# Calliope_mini_rev0_3_3_gipfel.net
KiCad netlist of a schematic drawn in EAGLE
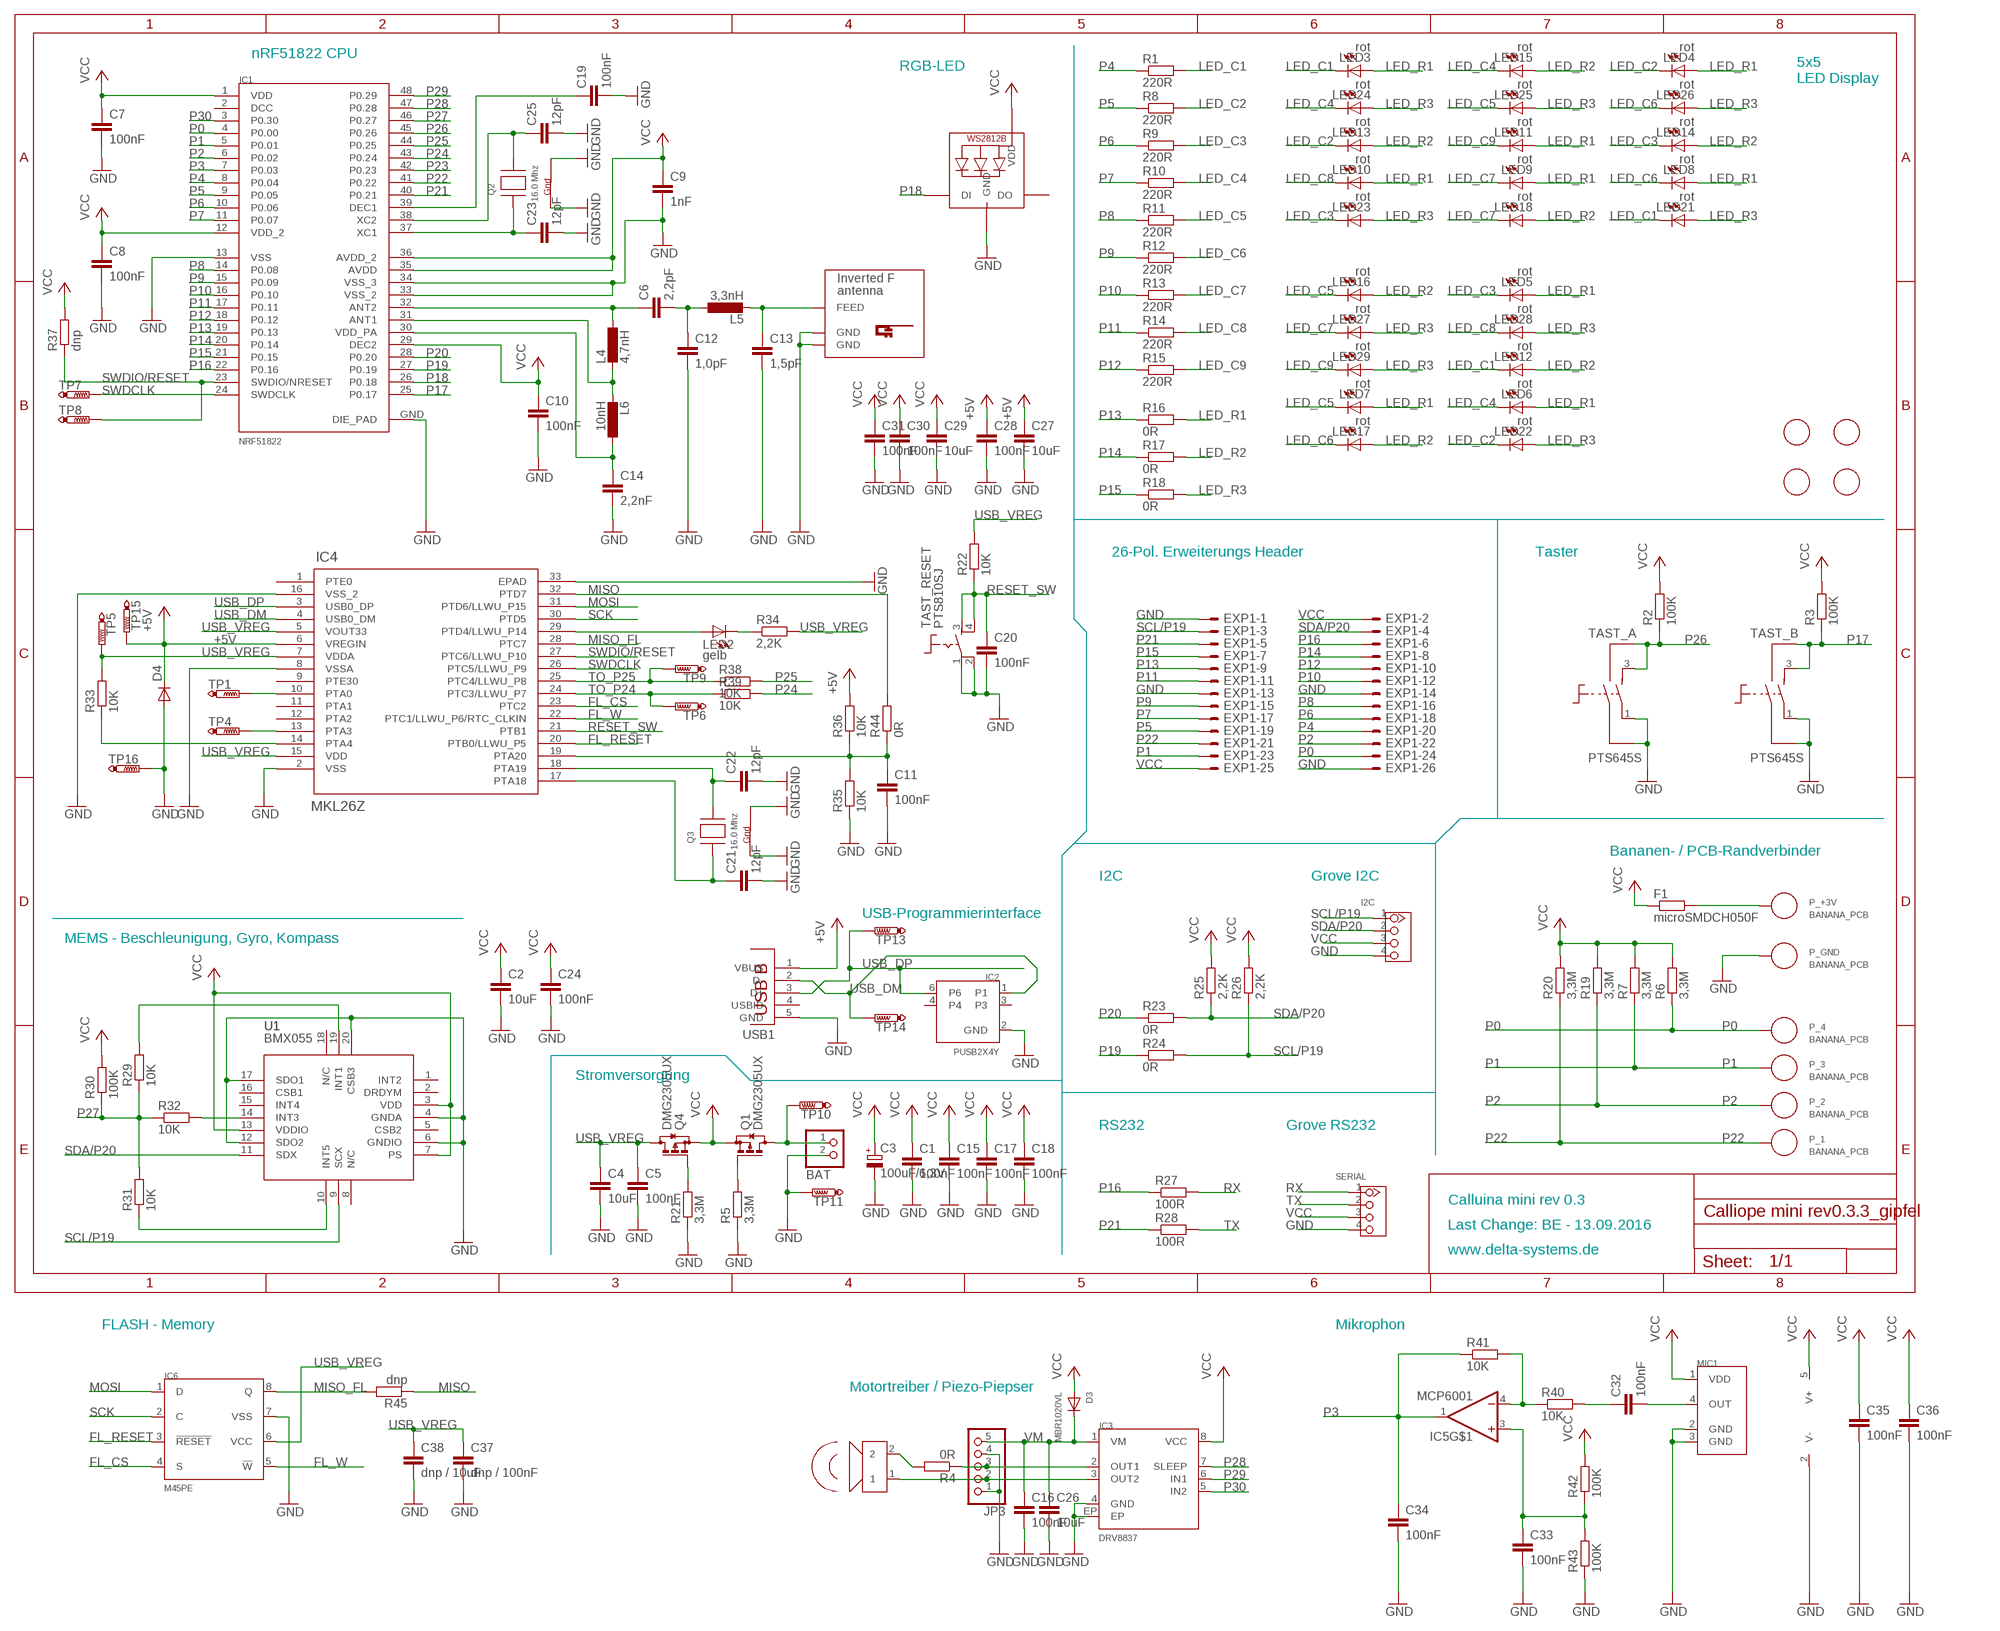
[diagram p0: schematic, sheet 1]

(export (version "E")
  (design (tool "Eeschema 10.0.6"))
  (components
    (comp (ref "BAT")
      (value "JST_2PIN-SMT-RA")
      (footprint "eagle-import:JST-PH-2-SMT-RA")
      (libsource (lib "eagle-import") (part "JST_2PIN-SMT-RA"))
    )
    (comp (ref "C1")
      (value "100nF")
      (footprint "eagle-import:0402")
      (libsource (lib "eagle-import") (part "C-EU0402"))
    )
    (comp (ref "C2")
      (value "10uF")
      (footprint "eagle-import:0603")
      (libsource (lib "eagle-import") (part "C-EU0603"))
    )
    (comp (ref "C3")
      (value "100uF/6,3V")
      (footprint "eagle-import:D_7343-31R")
      (libsource (lib "eagle-import") (part "CPOL-EUD/7343-31R"))
    )
    (comp (ref "C4")
      (value "10uF")
      (footprint "eagle-import:0603")
      (libsource (lib "eagle-import") (part "C-EU0603"))
    )
    (comp (ref "C5")
      (value "100nF")
      (footprint "eagle-import:0402")
      (libsource (lib "eagle-import") (part "C-EU0402"))
    )
    (comp (ref "C6")
      (value "2,2pF")
      (footprint "eagle-import:0402")
      (libsource (lib "eagle-import") (part "C-EU0402"))
    )
    (comp (ref "C7")
      (value "100nF")
      (footprint "eagle-import:0402")
      (libsource (lib "eagle-import") (part "C-EU0402"))
    )
    (comp (ref "C8")
      (value "100nF")
      (footprint "eagle-import:0402")
      (libsource (lib "eagle-import") (part "C-EU0402"))
    )
    (comp (ref "C9")
      (value "1nF")
      (footprint "eagle-import:0402")
      (libsource (lib "eagle-import") (part "C-EU0402"))
    )
    (comp (ref "C10")
      (value "100nF")
      (footprint "eagle-import:0402")
      (libsource (lib "eagle-import") (part "C-EU0402"))
    )
    (comp (ref "C11")
      (value "100nF")
      (footprint "eagle-import:0402")
      (libsource (lib "eagle-import") (part "C-EU0402"))
    )
    (comp (ref "C12")
      (value "1,0pF")
      (footprint "eagle-import:0402")
      (libsource (lib "eagle-import") (part "C-EU0402"))
    )
    (comp (ref "C13")
      (value "1,5pF")
      (footprint "eagle-import:0402")
      (libsource (lib "eagle-import") (part "C-EU0402"))
    )
    (comp (ref "C14")
      (value "2,2nF")
      (footprint "eagle-import:0402")
      (libsource (lib "eagle-import") (part "C-EU0402"))
    )
    (comp (ref "C15")
      (value "100nF")
      (footprint "eagle-import:0402")
      (libsource (lib "eagle-import") (part "C-EU0402"))
    )
    (comp (ref "C16")
      (value "100nF")
      (footprint "eagle-import:0402")
      (libsource (lib "eagle-import") (part "C-EU0402"))
    )
    (comp (ref "C17")
      (value "100nF")
      (footprint "eagle-import:0402")
      (libsource (lib "eagle-import") (part "C-EU0402"))
    )
    (comp (ref "C18")
      (value "100nF")
      (footprint "eagle-import:0402")
      (libsource (lib "eagle-import") (part "C-EU0402"))
    )
    (comp (ref "C19")
      (value "100nF")
      (footprint "eagle-import:0402")
      (libsource (lib "eagle-import") (part "C-EU0402"))
    )
    (comp (ref "C20")
      (value "100nF")
      (footprint "eagle-import:0402")
      (libsource (lib "eagle-import") (part "C-EU0402"))
    )
    (comp (ref "C21")
      (value "12pF")
      (footprint "eagle-import:0402")
      (libsource (lib "eagle-import") (part "C-EU0402"))
    )
    (comp (ref "C22")
      (value "12pF")
      (footprint "eagle-import:0402")
      (libsource (lib "eagle-import") (part "C-EU0402"))
    )
    (comp (ref "C23")
      (value "12pF")
      (footprint "eagle-import:0402")
      (libsource (lib "eagle-import") (part "C-EU0402"))
    )
    (comp (ref "C24")
      (value "100nF")
      (footprint "eagle-import:0402")
      (libsource (lib "eagle-import") (part "C-EU0402"))
    )
    (comp (ref "C25")
      (value "12pF")
      (footprint "eagle-import:0402")
      (libsource (lib "eagle-import") (part "C-EU0402"))
    )
    (comp (ref "C26")
      (value "10uF")
      (footprint "eagle-import:0603")
      (libsource (lib "eagle-import") (part "C-EU0603"))
    )
    (comp (ref "C27")
      (value "10uF")
      (footprint "eagle-import:0603")
      (libsource (lib "eagle-import") (part "C-EU0603"))
    )
    (comp (ref "C28")
      (value "100nF")
      (footprint "eagle-import:0402")
      (libsource (lib "eagle-import") (part "C-EU0402"))
    )
    (comp (ref "C29")
      (value "10uF")
      (footprint "eagle-import:0603")
      (libsource (lib "eagle-import") (part "C-EU0603"))
    )
    (comp (ref "C30")
      (value "100nF")
      (footprint "eagle-import:0402")
      (libsource (lib "eagle-import") (part "C-EU0402"))
    )
    (comp (ref "C31")
      (value "100nF")
      (footprint "eagle-import:0402")
      (libsource (lib "eagle-import") (part "C-EU0402"))
    )
    (comp (ref "C32")
      (value "100nF")
      (footprint "eagle-import:0402")
      (libsource (lib "eagle-import") (part "C-EU0402"))
    )
    (comp (ref "C33")
      (value "100nF")
      (footprint "eagle-import:0402")
      (libsource (lib "eagle-import") (part "C-EU0402"))
    )
    (comp (ref "C34")
      (value "100nF")
      (footprint "eagle-import:0402")
      (libsource (lib "eagle-import") (part "C-EU0402"))
    )
    (comp (ref "C35")
      (value "100nF")
      (footprint "eagle-import:0402")
      (libsource (lib "eagle-import") (part "C-EU0402"))
    )
    (comp (ref "C36")
      (value "100nF")
      (footprint "eagle-import:0402")
      (libsource (lib "eagle-import") (part "C-EU0402"))
    )
    (comp (ref "C37")
      (value "dnp / 100nF")
      (footprint "eagle-import:0402")
      (libsource (lib "eagle-import") (part "C-EU0402"))
    )
    (comp (ref "C38")
      (value "dnp / 10uF")
      (footprint "eagle-import:0603")
      (libsource (lib "eagle-import") (part "C-EU0603"))
    )
    (comp (ref "D3")
      (value "MBR1020VL")
      (footprint "eagle-import:SOD-123FL")
      (libsource (lib "eagle-import") (part "DIODE_SOD-123FL"))
    )
    (comp (ref "D4")
      (value "DIODE-SOD323-R")
      (footprint "eagle-import:SOD323-R")
      (libsource (lib "eagle-import") (part "DIODE-SOD323-R"))
    )
    (comp (ref "EXP1")
      (value "ML26E")
      (footprint "eagle-import:ML26")
      (libsource (lib "eagle-import") (part "ML26?E"))
    )
    (comp (ref "F1")
      (value "microSMDCH050F")
      (footprint "eagle-import:R1210")
      (libsource (lib "eagle-import") (part "R-EU_R1210"))
    )
    (comp (ref "I2C")
      (value "GROVE-CONNECTOR-DIP(4P-2.0)")
      (footprint "eagle-import:HW4-2.0")
      (libsource (lib "eagle-import") (part "GROVE-CONNECTOR-DIP(4P-2.0)"))
    )
    (comp (ref "IC1")
      (value "NRF51822")
      (footprint "eagle-import:QFN48")
      (libsource (lib "eagle-import") (part "NRF51822"))
    )
    (comp (ref "IC2")
      (value "PUSB2X4Y")
      (footprint "eagle-import:SOT363")
      (libsource (lib "eagle-import") (part "PUSB2X4Y"))
    )
    (comp (ref "IC3")
      (value "DRV8837")
      (footprint "eagle-import:WSON8")
      (libsource (lib "eagle-import") (part "DRV8837"))
    )
    (comp (ref "IC4")
      (value "MKL26Z")
      (footprint "eagle-import:QFN_32_5X5X0P9")
      (libsource (lib "eagle-import") (part "MKL26Z"))
    )
    (comp (ref "IC5")
      (value "MCP6001")
      (footprint "eagle-import:SOT23-5")
      (libsource (lib "eagle-import") (part "OPAMP_SINGLESOT23-5"))
    )
    (comp (ref "IC6")
      (value "M45PE")
      (footprint "eagle-import:VQFN8_6X5")
      (libsource (lib "eagle-import") (part "M45PE"))
    )
    (comp (ref "JP3")
      (value "PINHD-1X5")
      (footprint "eagle-import:1X05")
      (libsource (lib "eagle-import") (part "PINHD-1X5"))
    )
    (comp (ref "L4")
      (value "4,7nH")
      (footprint "eagle-import:0402")
      (libsource (lib "eagle-import") (part "L-EU0402"))
    )
    (comp (ref "L5")
      (value "3,3nH")
      (footprint "eagle-import:0402")
      (libsource (lib "eagle-import") (part "L-EU0402"))
    )
    (comp (ref "L6")
      (value "10nH")
      (footprint "eagle-import:0402")
      (libsource (lib "eagle-import") (part "L-EU0402"))
    )
    (comp (ref "LED1")
      (value "SK6812MINI")
      (footprint "eagle-import:LED3535")
      (libsource (lib "eagle-import") (part "WS2812B3535"))
    )
    (comp (ref "LED2")
      (value "gelb")
      (footprint "eagle-import:CHIPLED_0603")
      (libsource (lib "eagle-import") (part "LEDCHIPLED_0603"))
    )
    (comp (ref "LED3")
      (value "rot")
      (footprint "eagle-import:CHIPLED_0603")
      (libsource (lib "eagle-import") (part "LEDCHIPLED_0603"))
    )
    (comp (ref "LED4")
      (value "rot")
      (footprint "eagle-import:CHIPLED_0603")
      (libsource (lib "eagle-import") (part "LEDCHIPLED_0603"))
    )
    (comp (ref "LED5")
      (value "rot")
      (footprint "eagle-import:CHIPLED_0603")
      (libsource (lib "eagle-import") (part "LEDCHIPLED_0603"))
    )
    (comp (ref "LED6")
      (value "rot")
      (footprint "eagle-import:CHIPLED_0603")
      (libsource (lib "eagle-import") (part "LEDCHIPLED_0603"))
    )
    (comp (ref "LED7")
      (value "rot")
      (footprint "eagle-import:CHIPLED_0603")
      (libsource (lib "eagle-import") (part "LEDCHIPLED_0603"))
    )
    (comp (ref "LED8")
      (value "rot")
      (footprint "eagle-import:CHIPLED_0603")
      (libsource (lib "eagle-import") (part "LEDCHIPLED_0603"))
    )
    (comp (ref "LED9")
      (value "rot")
      (footprint "eagle-import:CHIPLED_0603")
      (libsource (lib "eagle-import") (part "LEDCHIPLED_0603"))
    )
    (comp (ref "LED10")
      (value "rot")
      (footprint "eagle-import:CHIPLED_0603")
      (libsource (lib "eagle-import") (part "LEDCHIPLED_0603"))
    )
    (comp (ref "LED11")
      (value "rot")
      (footprint "eagle-import:CHIPLED_0603")
      (libsource (lib "eagle-import") (part "LEDCHIPLED_0603"))
    )
    (comp (ref "LED12")
      (value "rot")
      (footprint "eagle-import:CHIPLED_0603")
      (libsource (lib "eagle-import") (part "LEDCHIPLED_0603"))
    )
    (comp (ref "LED13")
      (value "rot")
      (footprint "eagle-import:CHIPLED_0603")
      (libsource (lib "eagle-import") (part "LEDCHIPLED_0603"))
    )
    (comp (ref "LED14")
      (value "rot")
      (footprint "eagle-import:CHIPLED_0603")
      (libsource (lib "eagle-import") (part "LEDCHIPLED_0603"))
    )
    (comp (ref "LED15")
      (value "rot")
      (footprint "eagle-import:CHIPLED_0603")
      (libsource (lib "eagle-import") (part "LEDCHIPLED_0603"))
    )
    (comp (ref "LED16")
      (value "rot")
      (footprint "eagle-import:CHIPLED_0603")
      (libsource (lib "eagle-import") (part "LEDCHIPLED_0603"))
    )
    (comp (ref "LED17")
      (value "rot")
      (footprint "eagle-import:CHIPLED_0603")
      (libsource (lib "eagle-import") (part "LEDCHIPLED_0603"))
    )
    (comp (ref "LED18")
      (value "rot")
      (footprint "eagle-import:CHIPLED_0603")
      (libsource (lib "eagle-import") (part "LEDCHIPLED_0603"))
    )
    (comp (ref "LED21")
      (value "rot")
      (footprint "eagle-import:CHIPLED_0603")
      (libsource (lib "eagle-import") (part "LEDCHIPLED_0603"))
    )
    (comp (ref "LED22")
      (value "rot")
      (footprint "eagle-import:CHIPLED_0603")
      (libsource (lib "eagle-import") (part "LEDCHIPLED_0603"))
    )
    (comp (ref "LED23")
      (value "rot")
      (footprint "eagle-import:CHIPLED_0603")
      (libsource (lib "eagle-import") (part "LEDCHIPLED_0603"))
    )
    (comp (ref "LED24")
      (value "rot")
      (footprint "eagle-import:CHIPLED_0603")
      (libsource (lib "eagle-import") (part "LEDCHIPLED_0603"))
    )
    (comp (ref "LED25")
      (value "rot")
      (footprint "eagle-import:CHIPLED_0603")
      (libsource (lib "eagle-import") (part "LEDCHIPLED_0603"))
    )
    (comp (ref "LED26")
      (value "rot")
      (footprint "eagle-import:CHIPLED_0603")
      (libsource (lib "eagle-import") (part "LEDCHIPLED_0603"))
    )
    (comp (ref "LED27")
      (value "rot")
      (footprint "eagle-import:CHIPLED_0603")
      (libsource (lib "eagle-import") (part "LEDCHIPLED_0603"))
    )
    (comp (ref "LED28")
      (value "rot")
      (footprint "eagle-import:CHIPLED_0603")
      (libsource (lib "eagle-import") (part "LEDCHIPLED_0603"))
    )
    (comp (ref "LED29")
      (value "rot")
      (footprint "eagle-import:CHIPLED_0603")
      (libsource (lib "eagle-import") (part "LEDCHIPLED_0603"))
    )
    (comp (ref "MIC1")
      (value "SPU0410HR5H-PB")
      (footprint "eagle-import:SPU0410HR5H-PB")
      (libsource (lib "eagle-import") (part "SPU0410HR5H-PB"))
    )
    (comp (ref "P_+3V")
      (value "BANANA_PCB")
      (footprint "eagle-import:BANANA_REC")
      (libsource (lib "eagle-import") (part "BANANA_PCB"))
    )
    (comp (ref "P_1")
      (value "BANANA_PCB")
      (footprint "eagle-import:BANANA_REC")
      (libsource (lib "eagle-import") (part "BANANA_PCB"))
    )
    (comp (ref "P_2")
      (value "BANANA_PCB")
      (footprint "eagle-import:BANANA_REC")
      (libsource (lib "eagle-import") (part "BANANA_PCB"))
    )
    (comp (ref "P_3")
      (value "BANANA_PCB")
      (footprint "eagle-import:BANANA_REC")
      (libsource (lib "eagle-import") (part "BANANA_PCB"))
    )
    (comp (ref "P_4")
      (value "BANANA_PCB")
      (footprint "eagle-import:BANANA_REC")
      (libsource (lib "eagle-import") (part "BANANA_PCB"))
    )
    (comp (ref "P_GND")
      (value "BANANA_PCB")
      (footprint "eagle-import:BANANA_REC")
      (libsource (lib "eagle-import") (part "BANANA_PCB"))
    )
    (comp (ref "Q1")
      (value "DMG2305UX")
      (footprint "eagle-import:SOT23")
      (libsource (lib "eagle-import") (part "BSS84"))
    )
    (comp (ref "Q2")
      (value "16.0 Mhz")
      (footprint "eagle-import:NX3225")
      (libsource (lib "eagle-import") (part "XTAL-4-3225"))
    )
    (comp (ref "Q3")
      (value "16.0 Mhz")
      (footprint "eagle-import:NX3225")
      (libsource (lib "eagle-import") (part "XTAL-4-3225"))
    )
    (comp (ref "Q4")
      (value "DMG2305UX")
      (footprint "eagle-import:SOT23")
      (libsource (lib "eagle-import") (part "BSS84"))
    )
    (comp (ref "R1")
      (value "220R")
      (footprint "eagle-import:0402")
      (libsource (lib "eagle-import") (part "R-EU_0402"))
    )
    (comp (ref "R2")
      (value "100K")
      (footprint "eagle-import:0402")
      (libsource (lib "eagle-import") (part "R-EU_0402"))
    )
    (comp (ref "R3")
      (value "100K")
      (footprint "eagle-import:0402")
      (libsource (lib "eagle-import") (part "R-EU_0402"))
    )
    (comp (ref "R4")
      (value "0R")
      (footprint "eagle-import:0402")
      (libsource (lib "eagle-import") (part "R-EU_0402"))
    )
    (comp (ref "R5")
      (value "3,3M")
      (footprint "eagle-import:0402")
      (libsource (lib "eagle-import") (part "R-EU_0402"))
    )
    (comp (ref "R6")
      (value "3,3M")
      (footprint "eagle-import:0402")
      (libsource (lib "eagle-import") (part "R-EU_0402"))
    )
    (comp (ref "R7")
      (value "3,3M")
      (footprint "eagle-import:0402")
      (libsource (lib "eagle-import") (part "R-EU_0402"))
    )
    (comp (ref "R8")
      (value "220R")
      (footprint "eagle-import:0402")
      (libsource (lib "eagle-import") (part "R-EU_0402"))
    )
    (comp (ref "R9")
      (value "220R")
      (footprint "eagle-import:0402")
      (libsource (lib "eagle-import") (part "R-EU_0402"))
    )
    (comp (ref "R10")
      (value "220R")
      (footprint "eagle-import:0402")
      (libsource (lib "eagle-import") (part "R-EU_0402"))
    )
    (comp (ref "R11")
      (value "220R")
      (footprint "eagle-import:0402")
      (libsource (lib "eagle-import") (part "R-EU_0402"))
    )
    (comp (ref "R12")
      (value "220R")
      (footprint "eagle-import:0402")
      (libsource (lib "eagle-import") (part "R-EU_0402"))
    )
    (comp (ref "R13")
      (value "220R")
      (footprint "eagle-import:0402")
      (libsource (lib "eagle-import") (part "R-EU_0402"))
    )
    (comp (ref "R14")
      (value "220R")
      (footprint "eagle-import:0402")
      (libsource (lib "eagle-import") (part "R-EU_0402"))
    )
    (comp (ref "R15")
      (value "220R")
      (footprint "eagle-import:0402")
      (libsource (lib "eagle-import") (part "R-EU_0402"))
    )
    (comp (ref "R16")
      (value "0R")
      (footprint "eagle-import:0402")
      (libsource (lib "eagle-import") (part "R-EU_0402"))
    )
    (comp (ref "R17")
      (value "0R")
      (footprint "eagle-import:0402")
      (libsource (lib "eagle-import") (part "R-EU_0402"))
    )
    (comp (ref "R18")
      (value "0R")
      (footprint "eagle-import:0402")
      (libsource (lib "eagle-import") (part "R-EU_0402"))
    )
    (comp (ref "R19")
      (value "3,3M")
      (footprint "eagle-import:0402")
      (libsource (lib "eagle-import") (part "R-EU_0402"))
    )
    (comp (ref "R20")
      (value "3,3M")
      (footprint "eagle-import:0402")
      (libsource (lib "eagle-import") (part "R-EU_0402"))
    )
    (comp (ref "R21")
      (value "3,3M")
      (footprint "eagle-import:0402")
      (libsource (lib "eagle-import") (part "R-EU_0402"))
    )
    (comp (ref "R22")
      (value "10K")
      (footprint "eagle-import:0402")
      (libsource (lib "eagle-import") (part "R-EU_0402"))
    )
    (comp (ref "R23")
      (value "0R")
      (footprint "eagle-import:0402")
      (libsource (lib "eagle-import") (part "R-EU_0402"))
    )
    (comp (ref "R24")
      (value "0R")
      (footprint "eagle-import:0402")
      (libsource (lib "eagle-import") (part "R-EU_0402"))
    )
    (comp (ref "R25")
      (value "2,2K")
      (footprint "eagle-import:0402")
      (libsource (lib "eagle-import") (part "R-EU_0402"))
    )
    (comp (ref "R26")
      (value "2,2K")
      (footprint "eagle-import:0402")
      (libsource (lib "eagle-import") (part "R-EU_0402"))
    )
    (comp (ref "R27")
      (value "100R")
      (footprint "eagle-import:0402")
      (libsource (lib "eagle-import") (part "R-EU_0402"))
    )
    (comp (ref "R28")
      (value "100R")
      (footprint "eagle-import:0402")
      (libsource (lib "eagle-import") (part "R-EU_0402"))
    )
    (comp (ref "R29")
      (value "10K")
      (footprint "eagle-import:0402")
      (libsource (lib "eagle-import") (part "R-EU_0402"))
    )
    (comp (ref "R30")
      (value "100K")
      (footprint "eagle-import:0402")
      (libsource (lib "eagle-import") (part "R-EU_0402"))
    )
    (comp (ref "R31")
      (value "10K")
      (footprint "eagle-import:0402")
      (libsource (lib "eagle-import") (part "R-EU_0402"))
    )
    (comp (ref "R32")
      (value "10K")
      (footprint "eagle-import:0402")
      (libsource (lib "eagle-import") (part "R-EU_0402"))
    )
    (comp (ref "R33")
      (value "10K")
      (footprint "eagle-import:0402")
      (libsource (lib "eagle-import") (part "R-EU_0402"))
    )
    (comp (ref "R34")
      (value "2,2K")
      (footprint "eagle-import:0402")
      (libsource (lib "eagle-import") (part "R-EU_0402"))
    )
    (comp (ref "R35")
      (value "10K")
      (footprint "eagle-import:0402")
      (libsource (lib "eagle-import") (part "R-EU_0402"))
    )
    (comp (ref "R36")
      (value "10K")
      (footprint "eagle-import:0402")
      (libsource (lib "eagle-import") (part "R-EU_0402"))
    )
    (comp (ref "R37")
      (value "dnp")
      (footprint "eagle-import:0402")
      (libsource (lib "eagle-import") (part "R-EU_0402"))
    )
    (comp (ref "R38")
      (value "10K")
      (footprint "eagle-import:0402")
      (libsource (lib "eagle-import") (part "R-EU_0402"))
    )
    (comp (ref "R39")
      (value "10K")
      (footprint "eagle-import:0402")
      (libsource (lib "eagle-import") (part "R-EU_0402"))
    )
    (comp (ref "R40")
      (value "10K")
      (footprint "eagle-import:0402")
      (libsource (lib "eagle-import") (part "R-EU_0402"))
    )
    (comp (ref "R41")
      (value "10K")
      (footprint "eagle-import:0402")
      (libsource (lib "eagle-import") (part "R-EU_0402"))
    )
    (comp (ref "R42")
      (value "100K")
      (footprint "eagle-import:0402")
      (libsource (lib "eagle-import") (part "R-EU_0402"))
    )
    (comp (ref "R43")
      (value "100K")
      (footprint "eagle-import:0402")
      (libsource (lib "eagle-import") (part "R-EU_0402"))
    )
    (comp (ref "R44")
      (value "0R")
      (footprint "eagle-import:0402")
      (libsource (lib "eagle-import") (part "R-EU_0402"))
    )
    (comp (ref "R45")
      (value "dnp")
      (footprint "eagle-import:0402")
      (libsource (lib "eagle-import") (part "R-EU_0402"))
    )
    (comp (ref "SERIAL")
      (value "GROVE-CONNECTOR-DIP(4P-2.0)")
      (footprint "eagle-import:HW4-2.0")
      (libsource (lib "eagle-import") (part "GROVE-CONNECTOR-DIP(4P-2.0)"))
    )
    (comp (ref "SPK1")
      (value "PKMCS0909E4000-R1")
      (footprint "eagle-import:PKMCS")
      (libsource (lib "eagle-import") (part "PKMCS0909E4000-R1"))
    )
    (comp (ref "TAST_A")
      (value "PTS645S")
      (footprint "eagle-import:PTS645S")
      (libsource (lib "eagle-import") (part "PTS645S"))
    )
    (comp (ref "TAST_B")
      (value "PTS645S")
      (footprint "eagle-import:PTS645S")
      (libsource (lib "eagle-import") (part "PTS645S"))
    )
    (comp (ref "TAST_RESET")
      (value "PTS810SJ")
      (footprint "eagle-import:PTS810")
      (libsource (lib "eagle-import") (part "PTS810SJ"))
    )
    (comp (ref "TP1")
      (value "PTR1B1,27")
      (footprint "eagle-import:B1,27")
      (libsource (lib "eagle-import") (part "PTR1B1,27"))
    )
    (comp (ref "TP4")
      (value "PTR1B1,27")
      (footprint "eagle-import:B1,27")
      (libsource (lib "eagle-import") (part "PTR1B1,27"))
    )
    (comp (ref "TP5")
      (value "PTR1B1,27")
      (footprint "eagle-import:B1,27")
      (libsource (lib "eagle-import") (part "PTR1B1,27"))
    )
    (comp (ref "TP6")
      (value "PTR1B1,27")
      (footprint "eagle-import:B1,27")
      (libsource (lib "eagle-import") (part "PTR1B1,27"))
    )
    (comp (ref "TP7")
      (value "PTR1B1,27")
      (footprint "eagle-import:B1,27")
      (libsource (lib "eagle-import") (part "PTR1B1,27"))
    )
    (comp (ref "TP8")
      (value "PTR1B1,27")
      (footprint "eagle-import:B1,27")
      (libsource (lib "eagle-import") (part "PTR1B1,27"))
    )
    (comp (ref "TP9")
      (value "PTR1B1,27")
      (footprint "eagle-import:B1,27")
      (libsource (lib "eagle-import") (part "PTR1B1,27"))
    )
    (comp (ref "TP10")
      (value "PTR1B1,27")
      (footprint "eagle-import:B1,27")
      (libsource (lib "eagle-import") (part "PTR1B1,27"))
    )
    (comp (ref "TP11")
      (value "PTR1B1,27")
      (footprint "eagle-import:B1,27")
      (libsource (lib "eagle-import") (part "PTR1B1,27"))
    )
    (comp (ref "TP13")
      (value "PTR1B1,27")
      (footprint "eagle-import:B1,27")
      (libsource (lib "eagle-import") (part "PTR1B1,27"))
    )
    (comp (ref "TP14")
      (value "PTR1B1,27")
      (footprint "eagle-import:B1,27")
      (libsource (lib "eagle-import") (part "PTR1B1,27"))
    )
    (comp (ref "TP15")
      (value "PTR1B1,27")
      (footprint "eagle-import:B1,27")
      (libsource (lib "eagle-import") (part "PTR1B1,27"))
    )
    (comp (ref "TP16")
      (value "PTR1B1,27")
      (footprint "eagle-import:B1,27")
      (libsource (lib "eagle-import") (part "PTR1B1,27"))
    )
    (comp (ref "U$2")
      (value "INVERTED_F_ANTENNA")
      (footprint "eagle-import:DN0007+0_MIRROR")
      (libsource (lib "eagle-import") (part "INVERTED_F_ANTENNA"))
    )
    (comp (ref "U$5")
      (value "FIDUCIAL")
      (footprint "eagle-import:FIDUCIAL_1MM")
      (libsource (lib "eagle-import") (part "FIDUCIAL"))
    )
    (comp (ref "U$6")
      (value "FIDUCIAL")
      (footprint "eagle-import:FIDUCIAL_1MM")
      (libsource (lib "eagle-import") (part "FIDUCIAL"))
    )
    (comp (ref "U$7")
      (value "FIDUCIAL")
      (footprint "eagle-import:FIDUCIAL_1MM")
      (libsource (lib "eagle-import") (part "FIDUCIAL"))
    )
    (comp (ref "U$8")
      (value "FIDUCIAL")
      (footprint "eagle-import:FIDUCIAL_1MM")
      (libsource (lib "eagle-import") (part "FIDUCIAL"))
    )
    (comp (ref "U1")
      (value "BMX055")
      (footprint "eagle-import:BMX055")
      (libsource (lib "eagle-import") (part "BMX055"))
    )
    (comp (ref "USB1")
      (value "USB_47642-0011")
      (footprint "eagle-import:47642-0011")
      (libsource (lib "eagle-import") (part "USB_47642-0011"))
    )
  )
  (nets
    (net (code "1") (name "+5V") (class "Default")
      (node (ref "C27") (pin "1") (pinfunction "1_1") (pintype "passive"))
      (node (ref "C28") (pin "1") (pinfunction "1_1") (pintype "passive"))
      (node (ref "D4") (pin "C") (pinfunction "C_C") (pintype "passive"))
      (node (ref "IC4") (pin "6") (pinfunction "VREGIN_6") (pintype "input"))
      (node (ref "R36") (pin "2") (pinfunction "2_2") (pintype "passive"))
      (node (ref "TP15") (pin "TP") (pinfunction "TP_TP") (pintype "input"))
      (node (ref "USB1") (pin "1") (pinfunction "VBUS_1") (pintype "bidirectional"))
    )
    (net (code "2") (name "/FL_CS") (class "Default")
      (node (ref "IC4") (pin "23") (pinfunction "PTC2_23") (pintype "bidirectional"))
      (node (ref "IC6") (pin "4") (pinfunction "S_4") (pintype "bidirectional"))
    )
    (net (code "3") (name "/FL_RESET") (class "Default")
      (node (ref "IC4") (pin "20") (pinfunction "PTB0/LLWU_P5_20") (pintype "bidirectional"))
      (node (ref "IC6") (pin "3") (pinfunction "~{RESET}_3") (pintype "bidirectional"))
    )
    (net (code "4") (name "/FL_W") (class "Default")
      (node (ref "IC4") (pin "22") (pinfunction "PTC1/LLWU_P6/RTC_CLKIN_22") (pintype "bidirectional"))
      (node (ref "IC6") (pin "5") (pinfunction "~{W}_5") (pintype "bidirectional"))
    )
    (net (code "5") (name "/LED_C1") (class "Default")
      (node (ref "LED12") (pin "A") (pinfunction "A_A") (pintype "passive"))
      (node (ref "LED21") (pin "A") (pinfunction "A_A") (pintype "passive"))
      (node (ref "LED3") (pin "A") (pinfunction "A_A") (pintype "passive"))
      (node (ref "R1") (pin "2") (pinfunction "2_2") (pintype "passive"))
    )
    (net (code "6") (name "/LED_C2") (class "Default")
      (node (ref "LED13") (pin "A") (pinfunction "A_A") (pintype "passive"))
      (node (ref "LED22") (pin "A") (pinfunction "A_A") (pintype "passive"))
      (node (ref "LED4") (pin "A") (pinfunction "A_A") (pintype "passive"))
      (node (ref "R8") (pin "2") (pinfunction "2_2") (pintype "passive"))
    )
    (net (code "7") (name "/LED_C3") (class "Default")
      (node (ref "LED14") (pin "A") (pinfunction "A_A") (pintype "passive"))
      (node (ref "LED23") (pin "A") (pinfunction "A_A") (pintype "passive"))
      (node (ref "LED5") (pin "A") (pinfunction "A_A") (pintype "passive"))
      (node (ref "R9") (pin "2") (pinfunction "2_2") (pintype "passive"))
    )
    (net (code "8") (name "/LED_C4") (class "Default")
      (node (ref "LED15") (pin "A") (pinfunction "A_A") (pintype "passive"))
      (node (ref "LED24") (pin "A") (pinfunction "A_A") (pintype "passive"))
      (node (ref "LED6") (pin "A") (pinfunction "A_A") (pintype "passive"))
      (node (ref "R10") (pin "2") (pinfunction "2_2") (pintype "passive"))
    )
    (net (code "9") (name "/LED_C5") (class "Default")
      (node (ref "LED16") (pin "A") (pinfunction "A_A") (pintype "passive"))
      (node (ref "LED25") (pin "A") (pinfunction "A_A") (pintype "passive"))
      (node (ref "LED7") (pin "A") (pinfunction "A_A") (pintype "passive"))
      (node (ref "R11") (pin "2") (pinfunction "2_2") (pintype "passive"))
    )
    (net (code "10") (name "/LED_C6") (class "Default")
      (node (ref "LED17") (pin "A") (pinfunction "A_A") (pintype "passive"))
      (node (ref "LED26") (pin "A") (pinfunction "A_A") (pintype "passive"))
      (node (ref "LED8") (pin "A") (pinfunction "A_A") (pintype "passive"))
      (node (ref "R12") (pin "2") (pinfunction "2_2") (pintype "passive"))
    )
    (net (code "11") (name "/LED_C7") (class "Default")
      (node (ref "LED18") (pin "A") (pinfunction "A_A") (pintype "passive"))
      (node (ref "LED27") (pin "A") (pinfunction "A_A") (pintype "passive"))
      (node (ref "LED9") (pin "A") (pinfunction "A_A") (pintype "passive"))
      (node (ref "R13") (pin "2") (pinfunction "2_2") (pintype "passive"))
    )
    (net (code "12") (name "/LED_C8") (class "Default")
      (node (ref "LED10") (pin "A") (pinfunction "A_A") (pintype "passive"))
      (node (ref "LED28") (pin "A") (pinfunction "A_A") (pintype "passive"))
      (node (ref "R14") (pin "2") (pinfunction "2_2") (pintype "passive"))
    )
    (net (code "13") (name "/LED_C9") (class "Default")
      (node (ref "LED11") (pin "A") (pinfunction "A_A") (pintype "passive"))
      (node (ref "LED29") (pin "A") (pinfunction "A_A") (pintype "passive"))
      (node (ref "R15") (pin "2") (pinfunction "2_2") (pintype "passive"))
    )
    (net (code "14") (name "/LED_R1") (class "Default")
      (node (ref "LED10") (pin "C") (pinfunction "C_C") (pintype "passive"))
      (node (ref "LED11") (pin "C") (pinfunction "C_C") (pintype "passive"))
      (node (ref "LED3") (pin "C") (pinfunction "C_C") (pintype "passive"))
      (node (ref "LED4") (pin "C") (pinfunction "C_C") (pintype "passive"))
      (node (ref "LED5") (pin "C") (pinfunction "C_C") (pintype "passive"))
      (node (ref "LED6") (pin "C") (pinfunction "C_C") (pintype "passive"))
      (node (ref "LED7") (pin "C") (pinfunction "C_C") (pintype "passive"))
      (node (ref "LED8") (pin "C") (pinfunction "C_C") (pintype "passive"))
      (node (ref "LED9") (pin "C") (pinfunction "C_C") (pintype "passive"))
      (node (ref "R16") (pin "2") (pinfunction "2_2") (pintype "passive"))
    )
    (net (code "15") (name "/LED_R2") (class "Default")
      (node (ref "LED12") (pin "C") (pinfunction "C_C") (pintype "passive"))
      (node (ref "LED13") (pin "C") (pinfunction "C_C") (pintype "passive"))
      (node (ref "LED14") (pin "C") (pinfunction "C_C") (pintype "passive"))
      (node (ref "LED15") (pin "C") (pinfunction "C_C") (pintype "passive"))
      (node (ref "LED16") (pin "C") (pinfunction "C_C") (pintype "passive"))
      (node (ref "LED17") (pin "C") (pinfunction "C_C") (pintype "passive"))
      (node (ref "LED18") (pin "C") (pinfunction "C_C") (pintype "passive"))
      (node (ref "R17") (pin "2") (pinfunction "2_2") (pintype "passive"))
    )
    (net (code "16") (name "/LED_R3") (class "Default")
      (node (ref "LED21") (pin "C") (pinfunction "C_C") (pintype "passive"))
      (node (ref "LED22") (pin "C") (pinfunction "C_C") (pintype "passive"))
      (node (ref "LED23") (pin "C") (pinfunction "C_C") (pintype "passive"))
      (node (ref "LED24") (pin "C") (pinfunction "C_C") (pintype "passive"))
      (node (ref "LED25") (pin "C") (pinfunction "C_C") (pintype "passive"))
      (node (ref "LED26") (pin "C") (pinfunction "C_C") (pintype "passive"))
      (node (ref "LED27") (pin "C") (pinfunction "C_C") (pintype "passive"))
      (node (ref "LED28") (pin "C") (pinfunction "C_C") (pintype "passive"))
      (node (ref "LED29") (pin "C") (pinfunction "C_C") (pintype "passive"))
      (node (ref "R18") (pin "2") (pinfunction "2_2") (pintype "passive"))
    )
    (net (code "17") (name "/MISO") (class "Default")
      (node (ref "IC4") (pin "32") (pinfunction "PTD7_32") (pintype "bidirectional"))
      (node (ref "R44") (pin "2") (pinfunction "2_2") (pintype "passive"))
      (node (ref "R45") (pin "1") (pinfunction "1_1") (pintype "passive"))
    )
    (net (code "18") (name "/MISO_FL") (class "Default")
      (node (ref "IC4") (pin "28") (pinfunction "PTC7_28") (pintype "bidirectional"))
      (node (ref "IC6") (pin "8") (pinfunction "Q_8") (pintype "bidirectional"))
      (node (ref "R45") (pin "2") (pinfunction "2_2") (pintype "passive"))
    )
    (net (code "19") (name "/MOSI") (class "Default")
      (node (ref "IC4") (pin "31") (pinfunction "PTD6/LLWU_P15_31") (pintype "bidirectional"))
      (node (ref "IC6") (pin "1") (pinfunction "D_1") (pintype "bidirectional"))
    )
    (net (code "20") (name "/P0") (class "Default")
      (node (ref "EXP1") (pin "24") (pinfunction "S_24") (pintype "passive"))
      (node (ref "IC1") (pin "4") (pinfunction "P0.00_4") (pintype "bidirectional"))
      (node (ref "P_4") (pin "1") (pinfunction "1_1") (pintype "bidirectional"))
      (node (ref "R6") (pin "1") (pinfunction "1_1") (pintype "passive"))
    )
    (net (code "21") (name "/P1") (class "Default")
      (node (ref "EXP1") (pin "23") (pinfunction "S_23") (pintype "passive"))
      (node (ref "IC1") (pin "5") (pinfunction "P0.01_5") (pintype "bidirectional"))
      (node (ref "P_3") (pin "1") (pinfunction "1_1") (pintype "bidirectional"))
      (node (ref "R7") (pin "1") (pinfunction "1_1") (pintype "passive"))
    )
    (net (code "22") (name "/P2") (class "Default")
      (node (ref "EXP1") (pin "22") (pinfunction "S_22") (pintype "passive"))
      (node (ref "IC1") (pin "6") (pinfunction "P0.02_6") (pintype "bidirectional"))
      (node (ref "P_2") (pin "1") (pinfunction "1_1") (pintype "bidirectional"))
      (node (ref "R19") (pin "1") (pinfunction "1_1") (pintype "passive"))
    )
    (net (code "23") (name "/P3") (class "Default")
      (node (ref "C34") (pin "1") (pinfunction "1_1") (pintype "passive"))
      (node (ref "IC1") (pin "7") (pinfunction "P0.03_7") (pintype "bidirectional"))
      (node (ref "IC5") (pin "1") (pinfunction "OUT_1") (pintype "output"))
      (node (ref "R41") (pin "1") (pinfunction "1_1") (pintype "passive"))
    )
    (net (code "24") (name "/P4") (class "Default")
      (node (ref "EXP1") (pin "20") (pinfunction "S_20") (pintype "passive"))
      (node (ref "IC1") (pin "8") (pinfunction "P0.04_8") (pintype "bidirectional"))
      (node (ref "R1") (pin "1") (pinfunction "1_1") (pintype "passive"))
    )
    (net (code "25") (name "/P5") (class "Default")
      (node (ref "EXP1") (pin "19") (pinfunction "S_19") (pintype "passive"))
      (node (ref "IC1") (pin "9") (pinfunction "P0.05_9") (pintype "bidirectional"))
      (node (ref "R8") (pin "1") (pinfunction "1_1") (pintype "passive"))
    )
    (net (code "26") (name "/P6") (class "Default")
      (node (ref "EXP1") (pin "18") (pinfunction "S_18") (pintype "passive"))
      (node (ref "IC1") (pin "10") (pinfunction "P0.06_10") (pintype "bidirectional"))
      (node (ref "R9") (pin "1") (pinfunction "1_1") (pintype "passive"))
    )
    (net (code "27") (name "/P7") (class "Default")
      (node (ref "EXP1") (pin "17") (pinfunction "S_17") (pintype "passive"))
      (node (ref "IC1") (pin "11") (pinfunction "P0.07_11") (pintype "bidirectional"))
      (node (ref "R10") (pin "1") (pinfunction "1_1") (pintype "passive"))
    )
    (net (code "28") (name "/P8") (class "Default")
      (node (ref "EXP1") (pin "16") (pinfunction "S_16") (pintype "passive"))
      (node (ref "IC1") (pin "14") (pinfunction "P0.08_14") (pintype "bidirectional"))
      (node (ref "R11") (pin "1") (pinfunction "1_1") (pintype "passive"))
    )
    (net (code "29") (name "/P9") (class "Default")
      (node (ref "EXP1") (pin "15") (pinfunction "S_15") (pintype "passive"))
      (node (ref "IC1") (pin "15") (pinfunction "P0.09_15") (pintype "bidirectional"))
      (node (ref "R12") (pin "1") (pinfunction "1_1") (pintype "passive"))
    )
    (net (code "30") (name "/P10") (class "Default")
      (node (ref "EXP1") (pin "12") (pinfunction "S_12") (pintype "passive"))
      (node (ref "IC1") (pin "16") (pinfunction "P0.10_16") (pintype "bidirectional"))
      (node (ref "R13") (pin "1") (pinfunction "1_1") (pintype "passive"))
    )
    (net (code "31") (name "/P11") (class "Default")
      (node (ref "EXP1") (pin "11") (pinfunction "S_11") (pintype "passive"))
      (node (ref "IC1") (pin "17") (pinfunction "P0.11_17") (pintype "bidirectional"))
      (node (ref "R14") (pin "1") (pinfunction "1_1") (pintype "passive"))
    )
    (net (code "32") (name "/P12") (class "Default")
      (node (ref "EXP1") (pin "10") (pinfunction "S_10") (pintype "passive"))
      (node (ref "IC1") (pin "18") (pinfunction "P0.12_18") (pintype "bidirectional"))
      (node (ref "R15") (pin "1") (pinfunction "1_1") (pintype "passive"))
    )
    (net (code "33") (name "/P13") (class "Default")
      (node (ref "EXP1") (pin "9") (pinfunction "S_9") (pintype "passive"))
      (node (ref "IC1") (pin "19") (pinfunction "P0.13_19") (pintype "bidirectional"))
      (node (ref "R16") (pin "1") (pinfunction "1_1") (pintype "passive"))
    )
    (net (code "34") (name "/P14") (class "Default")
      (node (ref "EXP1") (pin "8") (pinfunction "S_8") (pintype "passive"))
      (node (ref "IC1") (pin "20") (pinfunction "P0.14_20") (pintype "bidirectional"))
      (node (ref "R17") (pin "1") (pinfunction "1_1") (pintype "passive"))
    )
    (net (code "35") (name "/P15") (class "Default")
      (node (ref "EXP1") (pin "7") (pinfunction "S_7") (pintype "passive"))
      (node (ref "IC1") (pin "21") (pinfunction "P0.15_21") (pintype "bidirectional"))
      (node (ref "R18") (pin "1") (pinfunction "1_1") (pintype "passive"))
    )
    (net (code "36") (name "/P16") (class "Default")
      (node (ref "EXP1") (pin "6") (pinfunction "S_6") (pintype "passive"))
      (node (ref "IC1") (pin "22") (pinfunction "P0.16_22") (pintype "bidirectional"))
      (node (ref "R27") (pin "1") (pinfunction "1_1") (pintype "passive"))
    )
    (net (code "37") (name "/P17") (class "Default")
      (node (ref "IC1") (pin "25") (pinfunction "P0.17_25") (pintype "bidirectional"))
      (node (ref "R3") (pin "1") (pinfunction "1_1") (pintype "passive"))
      (node (ref "TAST_B") (pin "3") (pinfunction "S1_3") (pintype "passive"))
      (node (ref "TAST_B") (pin "4") (pinfunction "S2_4") (pintype "passive"))
    )
    (net (code "38") (name "/P18") (class "Default")
      (node (ref "IC1") (pin "26") (pinfunction "P0.18_26") (pintype "bidirectional"))
      (node (ref "LED1") (pin "1") (pinfunction "DI_1") (pintype "input"))
    )
    (net (code "39") (name "/P19") (class "Default")
      (node (ref "IC1") (pin "27") (pinfunction "P0.19_27") (pintype "bidirectional"))
      (node (ref "R24") (pin "1") (pinfunction "1_1") (pintype "passive"))
    )
    (net (code "40") (name "/P20") (class "Default")
      (node (ref "IC1") (pin "28") (pinfunction "P0.20_28") (pintype "bidirectional"))
      (node (ref "R23") (pin "1") (pinfunction "1_1") (pintype "passive"))
    )
    (net (code "41") (name "/P21") (class "Default")
      (node (ref "EXP1") (pin "5") (pinfunction "S_5") (pintype "passive"))
      (node (ref "IC1") (pin "40") (pinfunction "P0.21_40") (pintype "bidirectional"))
      (node (ref "R28") (pin "1") (pinfunction "1_1") (pintype "passive"))
    )
    (net (code "42") (name "/P22") (class "Default")
      (node (ref "EXP1") (pin "21") (pinfunction "S_21") (pintype "passive"))
      (node (ref "IC1") (pin "41") (pinfunction "P0.22_41") (pintype "bidirectional"))
      (node (ref "P_1") (pin "1") (pinfunction "1_1") (pintype "bidirectional"))
      (node (ref "R20") (pin "1") (pinfunction "1_1") (pintype "passive"))
    )
    (net (code "43") (name "/P23") (class "Default")
      (node (ref "IC1") (pin "42") (pinfunction "P0.23_42") (pintype "bidirectional"))
    )
    (net (code "44") (name "/P24") (class "Default")
      (node (ref "IC1") (pin "43") (pinfunction "P0.24_43") (pintype "bidirectional"))
      (node (ref "R39") (pin "2") (pinfunction "2_2") (pintype "passive"))
    )
    (net (code "45") (name "/P25") (class "Default")
      (node (ref "IC1") (pin "44") (pinfunction "P0.25_44") (pintype "bidirectional"))
      (node (ref "R38") (pin "2") (pinfunction "2_2") (pintype "passive"))
    )
    (net (code "46") (name "/P26") (class "Default")
      (node (ref "IC1") (pin "45") (pinfunction "P0.26_45") (pintype "bidirectional"))
      (node (ref "R2") (pin "1") (pinfunction "1_1") (pintype "passive"))
      (node (ref "TAST_A") (pin "3") (pinfunction "S1_3") (pintype "passive"))
      (node (ref "TAST_A") (pin "4") (pinfunction "S2_4") (pintype "passive"))
    )
    (net (code "47") (name "/P27") (class "Default")
      (node (ref "IC1") (pin "46") (pinfunction "P0.27_46") (pintype "bidirectional"))
      (node (ref "R29") (pin "1") (pinfunction "1_1") (pintype "passive"))
      (node (ref "R30") (pin "1") (pinfunction "1_1") (pintype "passive"))
      (node (ref "R31") (pin "2") (pinfunction "2_2") (pintype "passive"))
      (node (ref "R32") (pin "1") (pinfunction "1_1") (pintype "passive"))
    )
    (net (code "48") (name "/P28") (class "Default")
      (node (ref "IC1") (pin "47") (pinfunction "P0.28_47") (pintype "bidirectional"))
      (node (ref "IC3") (pin "7") (pinfunction "SLEEP_7") (pintype "bidirectional"))
    )
    (net (code "49") (name "/P29") (class "Default")
      (node (ref "IC1") (pin "48") (pinfunction "P0.29_48") (pintype "bidirectional"))
      (node (ref "IC3") (pin "6") (pinfunction "IN1_6") (pintype "bidirectional"))
    )
    (net (code "50") (name "/P30") (class "Default")
      (node (ref "IC1") (pin "3") (pinfunction "P0.30_3") (pintype "bidirectional"))
      (node (ref "IC3") (pin "5") (pinfunction "IN2_5") (pintype "bidirectional"))
    )
    (net (code "51") (name "/RESET_SW") (class "Default")
      (node (ref "C20") (pin "1") (pinfunction "1_1") (pintype "passive"))
      (node (ref "IC4") (pin "21") (pinfunction "PTB1_21") (pintype "bidirectional"))
      (node (ref "R22") (pin "1") (pinfunction "1_1") (pintype "passive"))
      (node (ref "TAST_RESET") (pin "3") (pinfunction "S_3") (pintype "passive"))
      (node (ref "TAST_RESET") (pin "4") (pinfunction "S1_4") (pintype "passive"))
    )
    (net (code "52") (name "/RX") (class "Default")
      (node (ref "R27") (pin "2") (pinfunction "2_2") (pintype "passive"))
      (node (ref "SERIAL") (pin "1") (pinfunction "1_1") (pintype "bidirectional"))
    )
    (net (code "53") (name "/SCK") (class "Default")
      (node (ref "IC4") (pin "30") (pinfunction "PTD5_30") (pintype "bidirectional"))
      (node (ref "IC6") (pin "2") (pinfunction "C_2") (pintype "bidirectional"))
    )
    (net (code "54") (name "/SCL{slash}P19") (class "Default")
      (node (ref "EXP1") (pin "3") (pinfunction "S_3") (pintype "passive"))
      (node (ref "I2C") (pin "1") (pinfunction "1_1") (pintype "bidirectional"))
      (node (ref "R24") (pin "2") (pinfunction "2_2") (pintype "passive"))
      (node (ref "R26") (pin "1") (pinfunction "1_1") (pintype "passive"))
      (node (ref "U1") (pin "9") (pinfunction "SCX_9") (pintype "bidirectional"))
    )
    (net (code "55") (name "/SDA{slash}P20") (class "Default")
      (node (ref "EXP1") (pin "4") (pinfunction "S_4") (pintype "passive"))
      (node (ref "I2C") (pin "2") (pinfunction "2_2") (pintype "bidirectional"))
      (node (ref "R23") (pin "2") (pinfunction "2_2") (pintype "passive"))
      (node (ref "R25") (pin "1") (pinfunction "1_1") (pintype "passive"))
      (node (ref "U1") (pin "11") (pinfunction "SDX_11") (pintype "bidirectional"))
    )
    (net (code "56") (name "/SWDCLK") (class "Default")
      (node (ref "IC1") (pin "24") (pinfunction "SWDCLK_24") (pintype "bidirectional"))
      (node (ref "IC4") (pin "26") (pinfunction "PTC5/LLWU_P9_26") (pintype "bidirectional"))
      (node (ref "TP7") (pin "TP") (pinfunction "TP_TP") (pintype "input"))
    )
    (net (code "57") (name "/SWDIO{slash}RESET") (class "Default")
      (node (ref "IC1") (pin "23") (pinfunction "SWDIO/NRESET_23") (pintype "bidirectional"))
      (node (ref "IC4") (pin "27") (pinfunction "PTC6/LLWU_P10_27") (pintype "bidirectional"))
      (node (ref "R37") (pin "1") (pinfunction "1_1") (pintype "passive"))
      (node (ref "TP8") (pin "TP") (pinfunction "TP_TP") (pintype "input"))
    )
    (net (code "58") (name "/TO_P24") (class "Default")
      (node (ref "IC4") (pin "24") (pinfunction "PTC3/LLWU_P7_24") (pintype "bidirectional"))
      (node (ref "R39") (pin "1") (pinfunction "1_1") (pintype "passive"))
      (node (ref "TP6") (pin "TP") (pinfunction "TP_TP") (pintype "input"))
    )
    (net (code "59") (name "/TO_P25") (class "Default")
      (node (ref "IC4") (pin "25") (pinfunction "PTC4/LLWU_P8_25") (pintype "bidirectional"))
      (node (ref "R38") (pin "1") (pinfunction "1_1") (pintype "passive"))
      (node (ref "TP9") (pin "TP") (pinfunction "TP_TP") (pintype "input"))
    )
    (net (code "60") (name "/TX") (class "Default")
      (node (ref "R28") (pin "2") (pinfunction "2_2") (pintype "passive"))
      (node (ref "SERIAL") (pin "2") (pinfunction "2_2") (pintype "bidirectional"))
    )
    (net (code "61") (name "/USB_DM") (class "Default")
      (node (ref "IC2") (pin "1") (pinfunction "P1_1") (pintype "bidirectional"))
      (node (ref "IC4") (pin "4") (pinfunction "USB0_DM_4") (pintype "passive"))
      (node (ref "TP14") (pin "TP") (pinfunction "TP_TP") (pintype "input"))
      (node (ref "USB1") (pin "2") (pinfunction "D-_2") (pintype "bidirectional"))
    )
    (net (code "62") (name "/USB_DP") (class "Default")
      (node (ref "IC2") (pin "6") (pinfunction "P6_6") (pintype "bidirectional"))
      (node (ref "IC4") (pin "3") (pinfunction "USB0_DP_3") (pintype "passive"))
      (node (ref "TP13") (pin "TP") (pinfunction "TP_TP") (pintype "input"))
      (node (ref "USB1") (pin "3") (pinfunction "D+_3") (pintype "bidirectional"))
    )
    (net (code "63") (name "/USB_VREG") (class "Default")
      (node (ref "C37") (pin "1") (pinfunction "1_1") (pintype "passive"))
      (node (ref "C38") (pin "1") (pinfunction "1_1") (pintype "passive"))
      (node (ref "C4") (pin "1") (pinfunction "1_1") (pintype "passive"))
      (node (ref "C5") (pin "1") (pinfunction "1_1") (pintype "passive"))
      (node (ref "IC4") (pin "15") (pinfunction "VDD_15") (pintype "power_in"))
      (node (ref "IC4") (pin "5") (pinfunction "VOUT33_5") (pintype "output"))
      (node (ref "IC4") (pin "7") (pinfunction "VDDA_7") (pintype "power_in"))
      (node (ref "IC6") (pin "6") (pinfunction "VCC_6") (pintype "bidirectional"))
      (node (ref "Q4") (pin "3") (pinfunction "D_3") (pintype "passive"))
      (node (ref "R22") (pin "2") (pinfunction "2_2") (pintype "passive"))
      (node (ref "R33") (pin "2") (pinfunction "2_2") (pintype "passive"))
      (node (ref "R34") (pin "2") (pinfunction "2_2") (pintype "passive"))
      (node (ref "TP5") (pin "TP") (pinfunction "TP_TP") (pintype "input"))
    )
    (net (code "64") (name "/VM") (class "Default")
      (node (ref "C16") (pin "1") (pinfunction "1_1") (pintype "passive"))
      (node (ref "C26") (pin "1") (pinfunction "1_1") (pintype "passive"))
      (node (ref "D3") (pin "C") (pinfunction "C_C") (pintype "passive"))
      (node (ref "IC3") (pin "1") (pinfunction "VM_1") (pintype "bidirectional"))
      (node (ref "JP3") (pin "5") (pinfunction "5_5") (pintype "passive"))
    )
    (net (code "65") (name "GND") (class "Default")
      (node (ref "BAT") (pin "2") (pinfunction "1_2") (pintype "passive"))
      (node (ref "C1") (pin "2") (pinfunction "2_2") (pintype "passive"))
      (node (ref "C10") (pin "2") (pinfunction "2_2") (pintype "passive"))
      (node (ref "C11") (pin "2") (pinfunction "2_2") (pintype "passive"))
      (node (ref "C12") (pin "2") (pinfunction "2_2") (pintype "passive"))
      (node (ref "C13") (pin "2") (pinfunction "2_2") (pintype "passive"))
      (node (ref "C14") (pin "2") (pinfunction "2_2") (pintype "passive"))
      (node (ref "C15") (pin "2") (pinfunction "2_2") (pintype "passive"))
      (node (ref "C16") (pin "2") (pinfunction "2_2") (pintype "passive"))
      (node (ref "C17") (pin "2") (pinfunction "2_2") (pintype "passive"))
      (node (ref "C18") (pin "2") (pinfunction "2_2") (pintype "passive"))
      (node (ref "C19") (pin "2") (pinfunction "2_2") (pintype "passive"))
      (node (ref "C2") (pin "2") (pinfunction "2_2") (pintype "passive"))
      (node (ref "C20") (pin "2") (pinfunction "2_2") (pintype "passive"))
      (node (ref "C21") (pin "2") (pinfunction "2_2") (pintype "passive"))
      (node (ref "C22") (pin "2") (pinfunction "2_2") (pintype "passive"))
      (node (ref "C23") (pin "2") (pinfunction "2_2") (pintype "passive"))
      (node (ref "C24") (pin "2") (pinfunction "2_2") (pintype "passive"))
      (node (ref "C25") (pin "2") (pinfunction "2_2") (pintype "passive"))
      (node (ref "C26") (pin "2") (pinfunction "2_2") (pintype "passive"))
      (node (ref "C27") (pin "2") (pinfunction "2_2") (pintype "passive"))
      (node (ref "C28") (pin "2") (pinfunction "2_2") (pintype "passive"))
      (node (ref "C29") (pin "2") (pinfunction "2_2") (pintype "passive"))
      (node (ref "C3") (pin "-") (pinfunction "-_-") (pintype "passive"))
      (node (ref "C30") (pin "2") (pinfunction "2_2") (pintype "passive"))
      (node (ref "C31") (pin "2") (pinfunction "2_2") (pintype "passive"))
      (node (ref "C33") (pin "2") (pinfunction "2_2") (pintype "passive"))
      (node (ref "C34") (pin "2") (pinfunction "2_2") (pintype "passive"))
      (node (ref "C35") (pin "2") (pinfunction "2_2") (pintype "passive"))
      (node (ref "C36") (pin "2") (pinfunction "2_2") (pintype "passive"))
      (node (ref "C37") (pin "2") (pinfunction "2_2") (pintype "passive"))
      (node (ref "C38") (pin "2") (pinfunction "2_2") (pintype "passive"))
      (node (ref "C4") (pin "2") (pinfunction "2_2") (pintype "passive"))
      (node (ref "C5") (pin "2") (pinfunction "2_2") (pintype "passive"))
      (node (ref "C7") (pin "2") (pinfunction "2_2") (pintype "passive"))
      (node (ref "C8") (pin "2") (pinfunction "2_2") (pintype "passive"))
      (node (ref "C9") (pin "2") (pinfunction "2_2") (pintype "passive"))
      (node (ref "D4") (pin "A") (pinfunction "A_A") (pintype "passive"))
      (node (ref "EXP1") (pin "1") (pinfunction "S_1") (pintype "passive"))
      (node (ref "EXP1") (pin "13") (pinfunction "S_13") (pintype "passive"))
      (node (ref "EXP1") (pin "14") (pinfunction "S_14") (pintype "passive"))
      (node (ref "EXP1") (pin "26") (pinfunction "S_26") (pintype "passive"))
      (node (ref "I2C") (pin "4") (pinfunction "4_4") (pintype "bidirectional"))
      (node (ref "IC1") (pin "13") (pinfunction "VSS_13") (pintype "bidirectional"))
      (node (ref "IC1") (pin "33") (pinfunction "VSS_2_33") (pintype "bidirectional"))
      (node (ref "IC1") (pin "34") (pinfunction "VSS_3_34") (pintype "bidirectional"))
      (node (ref "IC1") (pin "GND") (pinfunction "DIE_PAD_GND") (pintype "bidirectional"))
      (node (ref "IC2") (pin "2") (pinfunction "GND_2") (pintype "bidirectional"))
      (node (ref "IC3") (pin "4") (pinfunction "GND_4") (pintype "bidirectional"))
      (node (ref "IC3") (pin "EP") (pinfunction "EP_EP") (pintype "bidirectional"))
      (node (ref "IC4") (pin "16") (pinfunction "VSS_2_16") (pintype "power_in"))
      (node (ref "IC4") (pin "2") (pinfunction "VSS_2") (pintype "power_in"))
      (node (ref "IC4") (pin "33") (pinfunction "EPAD_33") (pintype "passive"))
      (node (ref "IC4") (pin "8") (pinfunction "VSSA_8") (pintype "power_in"))
      (node (ref "IC5") (pin "2") (pinfunction "V-_2") (pintype "power_in"))
      (node (ref "IC6") (pin "7") (pinfunction "VSS_7") (pintype "bidirectional"))
      (node (ref "JP3") (pin "1") (pinfunction "1_1") (pintype "passive"))
      (node (ref "JP3") (pin "4") (pinfunction "4_4") (pintype "passive"))
      (node (ref "LED1") (pin "4") (pinfunction "GND_4") (pintype "power_in"))
      (node (ref "MIC1") (pin "2") (pinfunction "GND_2") (pintype "bidirectional"))
      (node (ref "MIC1") (pin "3") (pinfunction "GND_3") (pintype "bidirectional"))
      (node (ref "P_GND") (pin "1") (pinfunction "1_1") (pintype "bidirectional"))
      (node (ref "Q2") (pin "2") (pinfunction "G2_2") (pintype "power_in"))
      (node (ref "Q2") (pin "4") (pinfunction "G1_4") (pintype "power_in"))
      (node (ref "Q3") (pin "2") (pinfunction "G2_2") (pintype "power_in"))
      (node (ref "Q3") (pin "4") (pinfunction "G1_4") (pintype "power_in"))
      (node (ref "R21") (pin "1") (pinfunction "1_1") (pintype "passive"))
      (node (ref "R35") (pin "1") (pinfunction "1_1") (pintype "passive"))
      (node (ref "R43") (pin "1") (pinfunction "1_1") (pintype "passive"))
      (node (ref "R5") (pin "1") (pinfunction "1_1") (pintype "passive"))
      (node (ref "SERIAL") (pin "4") (pinfunction "4_4") (pintype "bidirectional"))
      (node (ref "TAST_A") (pin "1") (pinfunction "P1_1") (pintype "passive"))
      (node (ref "TAST_A") (pin "2") (pinfunction "P2_2") (pintype "passive"))
      (node (ref "TAST_B") (pin "1") (pinfunction "P1_1") (pintype "passive"))
      (node (ref "TAST_B") (pin "2") (pinfunction "P2_2") (pintype "passive"))
      (node (ref "TAST_RESET") (pin "1") (pinfunction "P_1") (pintype "passive"))
      (node (ref "TAST_RESET") (pin "2") (pinfunction "P1_2") (pintype "passive"))
      (node (ref "TP11") (pin "TP") (pinfunction "TP_TP") (pintype "input"))
      (node (ref "TP16") (pin "TP") (pinfunction "TP_TP") (pintype "input"))
      (node (ref "U$2") (pin "GND") (pinfunction "GND_GND") (pintype "bidirectional"))
      (node (ref "U$2") (pin "GND@1") (pinfunction "GND_GND@1") (pintype "bidirectional"))
      (node (ref "U1") (pin "12") (pinfunction "SDO2_12") (pintype "bidirectional"))
      (node (ref "U1") (pin "17") (pinfunction "SDO1_17") (pintype "bidirectional"))
      (node (ref "U1") (pin "20") (pinfunction "CSB3_20") (pintype "bidirectional"))
      (node (ref "U1") (pin "4") (pinfunction "GNDA_4") (pintype "bidirectional"))
      (node (ref "U1") (pin "6") (pinfunction "GNDIO_6") (pintype "bidirectional"))
      (node (ref "USB1") (pin "5") (pinfunction "GND_5") (pintype "bidirectional"))
    )
    (net (code "66") (name "Net-(BAT-2)") (class "Default")
      (node (ref "BAT") (pin "1") (pinfunction "2_1") (pintype "passive"))
      (node (ref "Q1") (pin "3") (pinfunction "D_3") (pintype "passive"))
      (node (ref "TP10") (pin "TP") (pinfunction "TP_TP") (pintype "input"))
    )
    (net (code "67") (name "Net-(C12-Pad1)") (class "Default")
      (node (ref "C12") (pin "1") (pinfunction "1_1") (pintype "passive"))
      (node (ref "C6") (pin "2") (pinfunction "2_2") (pintype "passive"))
      (node (ref "L5") (pin "1") (pinfunction "1_1") (pintype "passive"))
    )
    (net (code "68") (name "Net-(C13-Pad1)") (class "Default")
      (node (ref "C13") (pin "1") (pinfunction "1_1") (pintype "passive"))
      (node (ref "L5") (pin "2") (pinfunction "2_2") (pintype "passive"))
      (node (ref "U$2") (pin "FEED") (pinfunction "FEED_FEED") (pintype "bidirectional"))
    )
    (net (code "69") (name "Net-(C32-Pad1)") (class "Default")
      (node (ref "C32") (pin "1") (pinfunction "1_1") (pintype "passive"))
      (node (ref "R40") (pin "2") (pinfunction "2_2") (pintype "passive"))
    )
    (net (code "70") (name "Net-(F1-Pad2)") (class "Default")
      (node (ref "F1") (pin "2") (pinfunction "2_2") (pintype "passive"))
      (node (ref "P_+3V") (pin "1") (pinfunction "1_1") (pintype "bidirectional"))
    )
    (net (code "71") (name "Net-(IC1-ANT1)") (class "Default")
      (node (ref "IC1") (pin "31") (pinfunction "ANT1_31") (pintype "bidirectional"))
      (node (ref "L4") (pin "2") (pinfunction "2_2") (pintype "passive"))
      (node (ref "L6") (pin "2") (pinfunction "2_2") (pintype "passive"))
    )
    (net (code "72") (name "Net-(IC1-ANT2)") (class "Default")
      (node (ref "C6") (pin "1") (pinfunction "1_1") (pintype "passive"))
      (node (ref "IC1") (pin "32") (pinfunction "ANT2_32") (pintype "bidirectional"))
      (node (ref "L4") (pin "1") (pinfunction "1_1") (pintype "passive"))
    )
    (net (code "73") (name "Net-(IC1-DEC1)") (class "Default")
      (node (ref "C19") (pin "1") (pinfunction "1_1") (pintype "passive"))
      (node (ref "IC1") (pin "39") (pinfunction "DEC1_39") (pintype "bidirectional"))
    )
    (net (code "74") (name "Net-(IC1-VDD_PA)") (class "Default")
      (node (ref "C14") (pin "1") (pinfunction "1_1") (pintype "passive"))
      (node (ref "IC1") (pin "30") (pinfunction "VDD_PA_30") (pintype "bidirectional"))
      (node (ref "L6") (pin "1") (pinfunction "1_1") (pintype "passive"))
    )
    (net (code "75") (name "Net-(IC1-XC1)") (class "Default")
      (node (ref "C23") (pin "1") (pinfunction "1_1") (pintype "passive"))
      (node (ref "IC1") (pin "37") (pinfunction "XC1_37") (pintype "bidirectional"))
      (node (ref "Q2") (pin "1") (pinfunction "X1_1") (pintype "bidirectional"))
    )
    (net (code "76") (name "Net-(IC1-XC2)") (class "Default")
      (node (ref "C25") (pin "1") (pinfunction "1_1") (pintype "passive"))
      (node (ref "IC1") (pin "38") (pinfunction "XC2_38") (pintype "bidirectional"))
      (node (ref "Q2") (pin "3") (pinfunction "X2_3") (pintype "bidirectional"))
    )
    (net (code "77") (name "Net-(IC3-OUT1)") (class "Default")
      (node (ref "IC3") (pin "2") (pinfunction "OUT1_2") (pintype "bidirectional"))
      (node (ref "JP3") (pin "3") (pinfunction "3_3") (pintype "passive"))
      (node (ref "R4") (pin "1") (pinfunction "1_1") (pintype "passive"))
    )
    (net (code "78") (name "Net-(IC3-OUT2)") (class "Default")
      (node (ref "IC3") (pin "3") (pinfunction "OUT2_3") (pintype "bidirectional"))
      (node (ref "JP3") (pin "2") (pinfunction "2_2") (pintype "passive"))
      (node (ref "SPK1") (pin "1") (pinfunction "1_1") (pintype "bidirectional"))
    )
    (net (code "79") (name "Net-(IC4-PTA0)") (class "Default")
      (node (ref "IC4") (pin "10") (pinfunction "PTA0_10") (pintype "bidirectional"))
      (node (ref "TP1") (pin "TP") (pinfunction "TP_TP") (pintype "input"))
    )
    (net (code "80") (name "Net-(IC4-PTA3)") (class "Default")
      (node (ref "IC4") (pin "13") (pinfunction "PTA3_13") (pintype "bidirectional"))
      (node (ref "TP4") (pin "TP") (pinfunction "TP_TP") (pintype "input"))
    )
    (net (code "81") (name "Net-(IC4-PTA4)") (class "Default")
      (node (ref "IC4") (pin "14") (pinfunction "PTA4_14") (pintype "bidirectional"))
      (node (ref "R33") (pin "1") (pinfunction "1_1") (pintype "passive"))
    )
    (net (code "82") (name "Net-(IC4-PTA18)") (class "Default")
      (node (ref "C21") (pin "1") (pinfunction "1_1") (pintype "passive"))
      (node (ref "IC4") (pin "17") (pinfunction "PTA18_17") (pintype "bidirectional"))
      (node (ref "Q3") (pin "1") (pinfunction "X1_1") (pintype "bidirectional"))
    )
    (net (code "83") (name "Net-(IC4-PTA19)") (class "Default")
      (node (ref "C22") (pin "1") (pinfunction "1_1") (pintype "passive"))
      (node (ref "IC4") (pin "18") (pinfunction "PTA19_18") (pintype "bidirectional"))
      (node (ref "Q3") (pin "3") (pinfunction "X2_3") (pintype "bidirectional"))
    )
    (net (code "84") (name "Net-(IC4-PTA20)") (class "Default")
      (node (ref "C11") (pin "1") (pinfunction "1_1") (pintype "passive"))
      (node (ref "IC4") (pin "19") (pinfunction "PTA20_19") (pintype "bidirectional"))
      (node (ref "R35") (pin "2") (pinfunction "2_2") (pintype "passive"))
      (node (ref "R36") (pin "1") (pinfunction "1_1") (pintype "passive"))
      (node (ref "R44") (pin "1") (pinfunction "1_1") (pintype "passive"))
    )
    (net (code "85") (name "Net-(IC4-PTD4{slash}LLWU_P14)") (class "Default")
      (node (ref "IC4") (pin "29") (pinfunction "PTD4/LLWU_P14_29") (pintype "bidirectional"))
      (node (ref "LED2") (pin "C") (pinfunction "C_C") (pintype "passive"))
    )
    (net (code "86") (name "Net-(IC5A-+IN)") (class "Default")
      (node (ref "C33") (pin "1") (pinfunction "1_1") (pintype "passive"))
      (node (ref "IC5") (pin "3") (pinfunction "+IN_3") (pintype "input"))
      (node (ref "R42") (pin "1") (pinfunction "1_1") (pintype "passive"))
      (node (ref "R43") (pin "2") (pinfunction "2_2") (pintype "passive"))
    )
    (net (code "87") (name "Net-(IC5A--IN)") (class "Default")
      (node (ref "IC5") (pin "4") (pinfunction "-IN_4") (pintype "input"))
      (node (ref "R40") (pin "1") (pinfunction "1_1") (pintype "passive"))
      (node (ref "R41") (pin "2") (pinfunction "2_2") (pintype "passive"))
    )
    (net (code "88") (name "Net-(LED2-PadA)") (class "Default")
      (node (ref "LED2") (pin "A") (pinfunction "A_A") (pintype "passive"))
      (node (ref "R34") (pin "1") (pinfunction "1_1") (pintype "passive"))
    )
    (net (code "89") (name "Net-(MIC1-OUT)") (class "Default")
      (node (ref "C32") (pin "2") (pinfunction "2_2") (pintype "passive"))
      (node (ref "MIC1") (pin "4") (pinfunction "OUT_4") (pintype "bidirectional"))
    )
    (net (code "90") (name "Net-(Q1-G)") (class "Default")
      (node (ref "Q1") (pin "1") (pinfunction "G_1") (pintype "passive"))
      (node (ref "R5") (pin "2") (pinfunction "2_2") (pintype "passive"))
    )
    (net (code "91") (name "Net-(Q4-G)") (class "Default")
      (node (ref "Q4") (pin "1") (pinfunction "G_1") (pintype "passive"))
      (node (ref "R21") (pin "2") (pinfunction "2_2") (pintype "passive"))
    )
    (net (code "92") (name "Net-(R4-Pad2)") (class "Default")
      (node (ref "R4") (pin "2") (pinfunction "2_2") (pintype "passive"))
      (node (ref "SPK1") (pin "2") (pinfunction "2_2") (pintype "bidirectional"))
    )
    (net (code "93") (name "Net-(U1-INT1)") (class "Default")
      (node (ref "R29") (pin "2") (pinfunction "2_2") (pintype "passive"))
      (node (ref "U1") (pin "19") (pinfunction "INT1_19") (pintype "bidirectional"))
    )
    (net (code "94") (name "Net-(U1-INT3)") (class "Default")
      (node (ref "R32") (pin "2") (pinfunction "2_2") (pintype "passive"))
      (node (ref "U1") (pin "14") (pinfunction "INT3_14") (pintype "bidirectional"))
    )
    (net (code "95") (name "Net-(U1-INT5)") (class "Default")
      (node (ref "R31") (pin "1") (pinfunction "1_1") (pintype "passive"))
      (node (ref "U1") (pin "10") (pinfunction "INT5_10") (pintype "bidirectional"))
    )
    (net (code "96") (name "VCC") (class "Default")
      (node (ref "C1") (pin "1") (pinfunction "1_1") (pintype "passive"))
      (node (ref "C10") (pin "1") (pinfunction "1_1") (pintype "passive"))
      (node (ref "C15") (pin "1") (pinfunction "1_1") (pintype "passive"))
      (node (ref "C17") (pin "1") (pinfunction "1_1") (pintype "passive"))
      (node (ref "C18") (pin "1") (pinfunction "1_1") (pintype "passive"))
      (node (ref "C2") (pin "1") (pinfunction "1_1") (pintype "passive"))
      (node (ref "C24") (pin "1") (pinfunction "1_1") (pintype "passive"))
      (node (ref "C29") (pin "1") (pinfunction "1_1") (pintype "passive"))
      (node (ref "C3") (pin "+") (pinfunction "+_+") (pintype "passive"))
      (node (ref "C30") (pin "1") (pinfunction "1_1") (pintype "passive"))
      (node (ref "C31") (pin "1") (pinfunction "1_1") (pintype "passive"))
      (node (ref "C35") (pin "1") (pinfunction "1_1") (pintype "passive"))
      (node (ref "C36") (pin "1") (pinfunction "1_1") (pintype "passive"))
      (node (ref "C7") (pin "1") (pinfunction "1_1") (pintype "passive"))
      (node (ref "C8") (pin "1") (pinfunction "1_1") (pintype "passive"))
      (node (ref "C9") (pin "1") (pinfunction "1_1") (pintype "passive"))
      (node (ref "D3") (pin "A") (pinfunction "A_A") (pintype "passive"))
      (node (ref "EXP1") (pin "2") (pinfunction "S_2") (pintype "passive"))
      (node (ref "EXP1") (pin "25") (pinfunction "S_25") (pintype "passive"))
      (node (ref "F1") (pin "1") (pinfunction "1_1") (pintype "passive"))
      (node (ref "I2C") (pin "3") (pinfunction "3_3") (pintype "bidirectional"))
      (node (ref "IC1") (pin "1") (pinfunction "VDD_1") (pintype "bidirectional"))
      (node (ref "IC1") (pin "12") (pinfunction "VDD_2_12") (pintype "bidirectional"))
      (node (ref "IC1") (pin "29") (pinfunction "DEC2_29") (pintype "bidirectional"))
      (node (ref "IC1") (pin "35") (pinfunction "AVDD_35") (pintype "bidirectional"))
      (node (ref "IC1") (pin "36") (pinfunction "AVDD_2_36") (pintype "bidirectional"))
      (node (ref "IC3") (pin "8") (pinfunction "VCC_8") (pintype "bidirectional"))
      (node (ref "IC5") (pin "5") (pinfunction "V+_5") (pintype "power_in"))
      (node (ref "LED1") (pin "2") (pinfunction "VDD_2") (pintype "power_in"))
      (node (ref "MIC1") (pin "1") (pinfunction "VDD_1") (pintype "bidirectional"))
      (node (ref "Q1") (pin "2") (pinfunction "S_2") (pintype "passive"))
      (node (ref "Q4") (pin "2") (pinfunction "S_2") (pintype "passive"))
      (node (ref "R19") (pin "2") (pinfunction "2_2") (pintype "passive"))
      (node (ref "R2") (pin "2") (pinfunction "2_2") (pintype "passive"))
      (node (ref "R20") (pin "2") (pinfunction "2_2") (pintype "passive"))
      (node (ref "R25") (pin "2") (pinfunction "2_2") (pintype "passive"))
      (node (ref "R26") (pin "2") (pinfunction "2_2") (pintype "passive"))
      (node (ref "R3") (pin "2") (pinfunction "2_2") (pintype "passive"))
      (node (ref "R30") (pin "2") (pinfunction "2_2") (pintype "passive"))
      (node (ref "R37") (pin "2") (pinfunction "2_2") (pintype "passive"))
      (node (ref "R42") (pin "2") (pinfunction "2_2") (pintype "passive"))
      (node (ref "R6") (pin "2") (pinfunction "2_2") (pintype "passive"))
      (node (ref "R7") (pin "2") (pinfunction "2_2") (pintype "passive"))
      (node (ref "SERIAL") (pin "3") (pinfunction "3_3") (pintype "bidirectional"))
      (node (ref "U1") (pin "13") (pinfunction "VDDIO_13") (pintype "bidirectional"))
      (node (ref "U1") (pin "3") (pinfunction "VDD_3") (pintype "bidirectional"))
      (node (ref "U1") (pin "7") (pinfunction "PS_7") (pintype "bidirectional"))
    )
    (net (code "97") (name "unconnected-(IC1-DCC-Pad2)") (class "Default")
      (node (ref "IC1") (pin "2") (pinfunction "DCC_2") (pintype "bidirectional"))
    )
    (net (code "98") (name "unconnected-(IC2-P3-Pad3)") (class "Default")
      (node (ref "IC2") (pin "3") (pinfunction "P3_3") (pintype "bidirectional"))
    )
    (net (code "99") (name "unconnected-(IC2-P4-Pad4)") (class "Default")
      (node (ref "IC2") (pin "4") (pinfunction "P4_4") (pintype "bidirectional"))
    )
    (net (code "100") (name "unconnected-(IC4-PTA1-Pad11)") (class "Default")
      (node (ref "IC4") (pin "11") (pinfunction "PTA1_11") (pintype "bidirectional"))
    )
    (net (code "101") (name "unconnected-(IC4-PTA2-Pad12)") (class "Default")
      (node (ref "IC4") (pin "12") (pinfunction "PTA2_12") (pintype "bidirectional"))
    )
    (net (code "102") (name "unconnected-(IC4-PTE0-Pad1)") (class "Default")
      (node (ref "IC4") (pin "1") (pinfunction "PTE0_1") (pintype "bidirectional"))
    )
    (net (code "103") (name "unconnected-(IC4-PTE30-Pad9)") (class "Default")
      (node (ref "IC4") (pin "9") (pinfunction "PTE30_9") (pintype "bidirectional"))
    )
    (net (code "104") (name "unconnected-(LED1-DO-Pad3)") (class "Default")
      (node (ref "LED1") (pin "3") (pinfunction "DO_3") (pintype "output"))
    )
    (net (code "105") (name "unconnected-(U1-CSB1-Pad16)") (class "Default")
      (node (ref "U1") (pin "16") (pinfunction "CSB1_16") (pintype "bidirectional"))
    )
    (net (code "106") (name "unconnected-(U1-CSB2-Pad5)") (class "Default")
      (node (ref "U1") (pin "5") (pinfunction "CSB2_5") (pintype "bidirectional"))
    )
    (net (code "107") (name "unconnected-(U1-DRDYM-Pad2)") (class "Default")
      (node (ref "U1") (pin "2") (pinfunction "DRDYM_2") (pintype "bidirectional"))
    )
    (net (code "108") (name "unconnected-(U1-INT2-Pad1)") (class "Default")
      (node (ref "U1") (pin "1") (pinfunction "INT2_1") (pintype "bidirectional"))
    )
    (net (code "109") (name "unconnected-(U1-INT4-Pad15)") (class "Default")
      (node (ref "U1") (pin "15") (pinfunction "INT4_15") (pintype "bidirectional"))
    )
    (net (code "110") (name "unconnected-(U1-N{slash}C-Pad8)") (class "Default")
      (node (ref "U1") (pin "8") (pinfunction "N/C_8") (pintype "bidirectional"))
    )
    (net (code "111") (name "unconnected-(U1-N{slash}C-Pad18)") (class "Default")
      (node (ref "U1") (pin "18") (pinfunction "N/C_18") (pintype "bidirectional"))
    )
    (net (code "112") (name "unconnected-(USB1-USBID-Pad4)") (class "Default")
      (node (ref "USB1") (pin "4") (pinfunction "USBID_4") (pintype "bidirectional"))
    )
  )
)
